# Kit_ELO_DEVMPDv1.net
KiCad netlist of a schematic drawn in Altium Designer
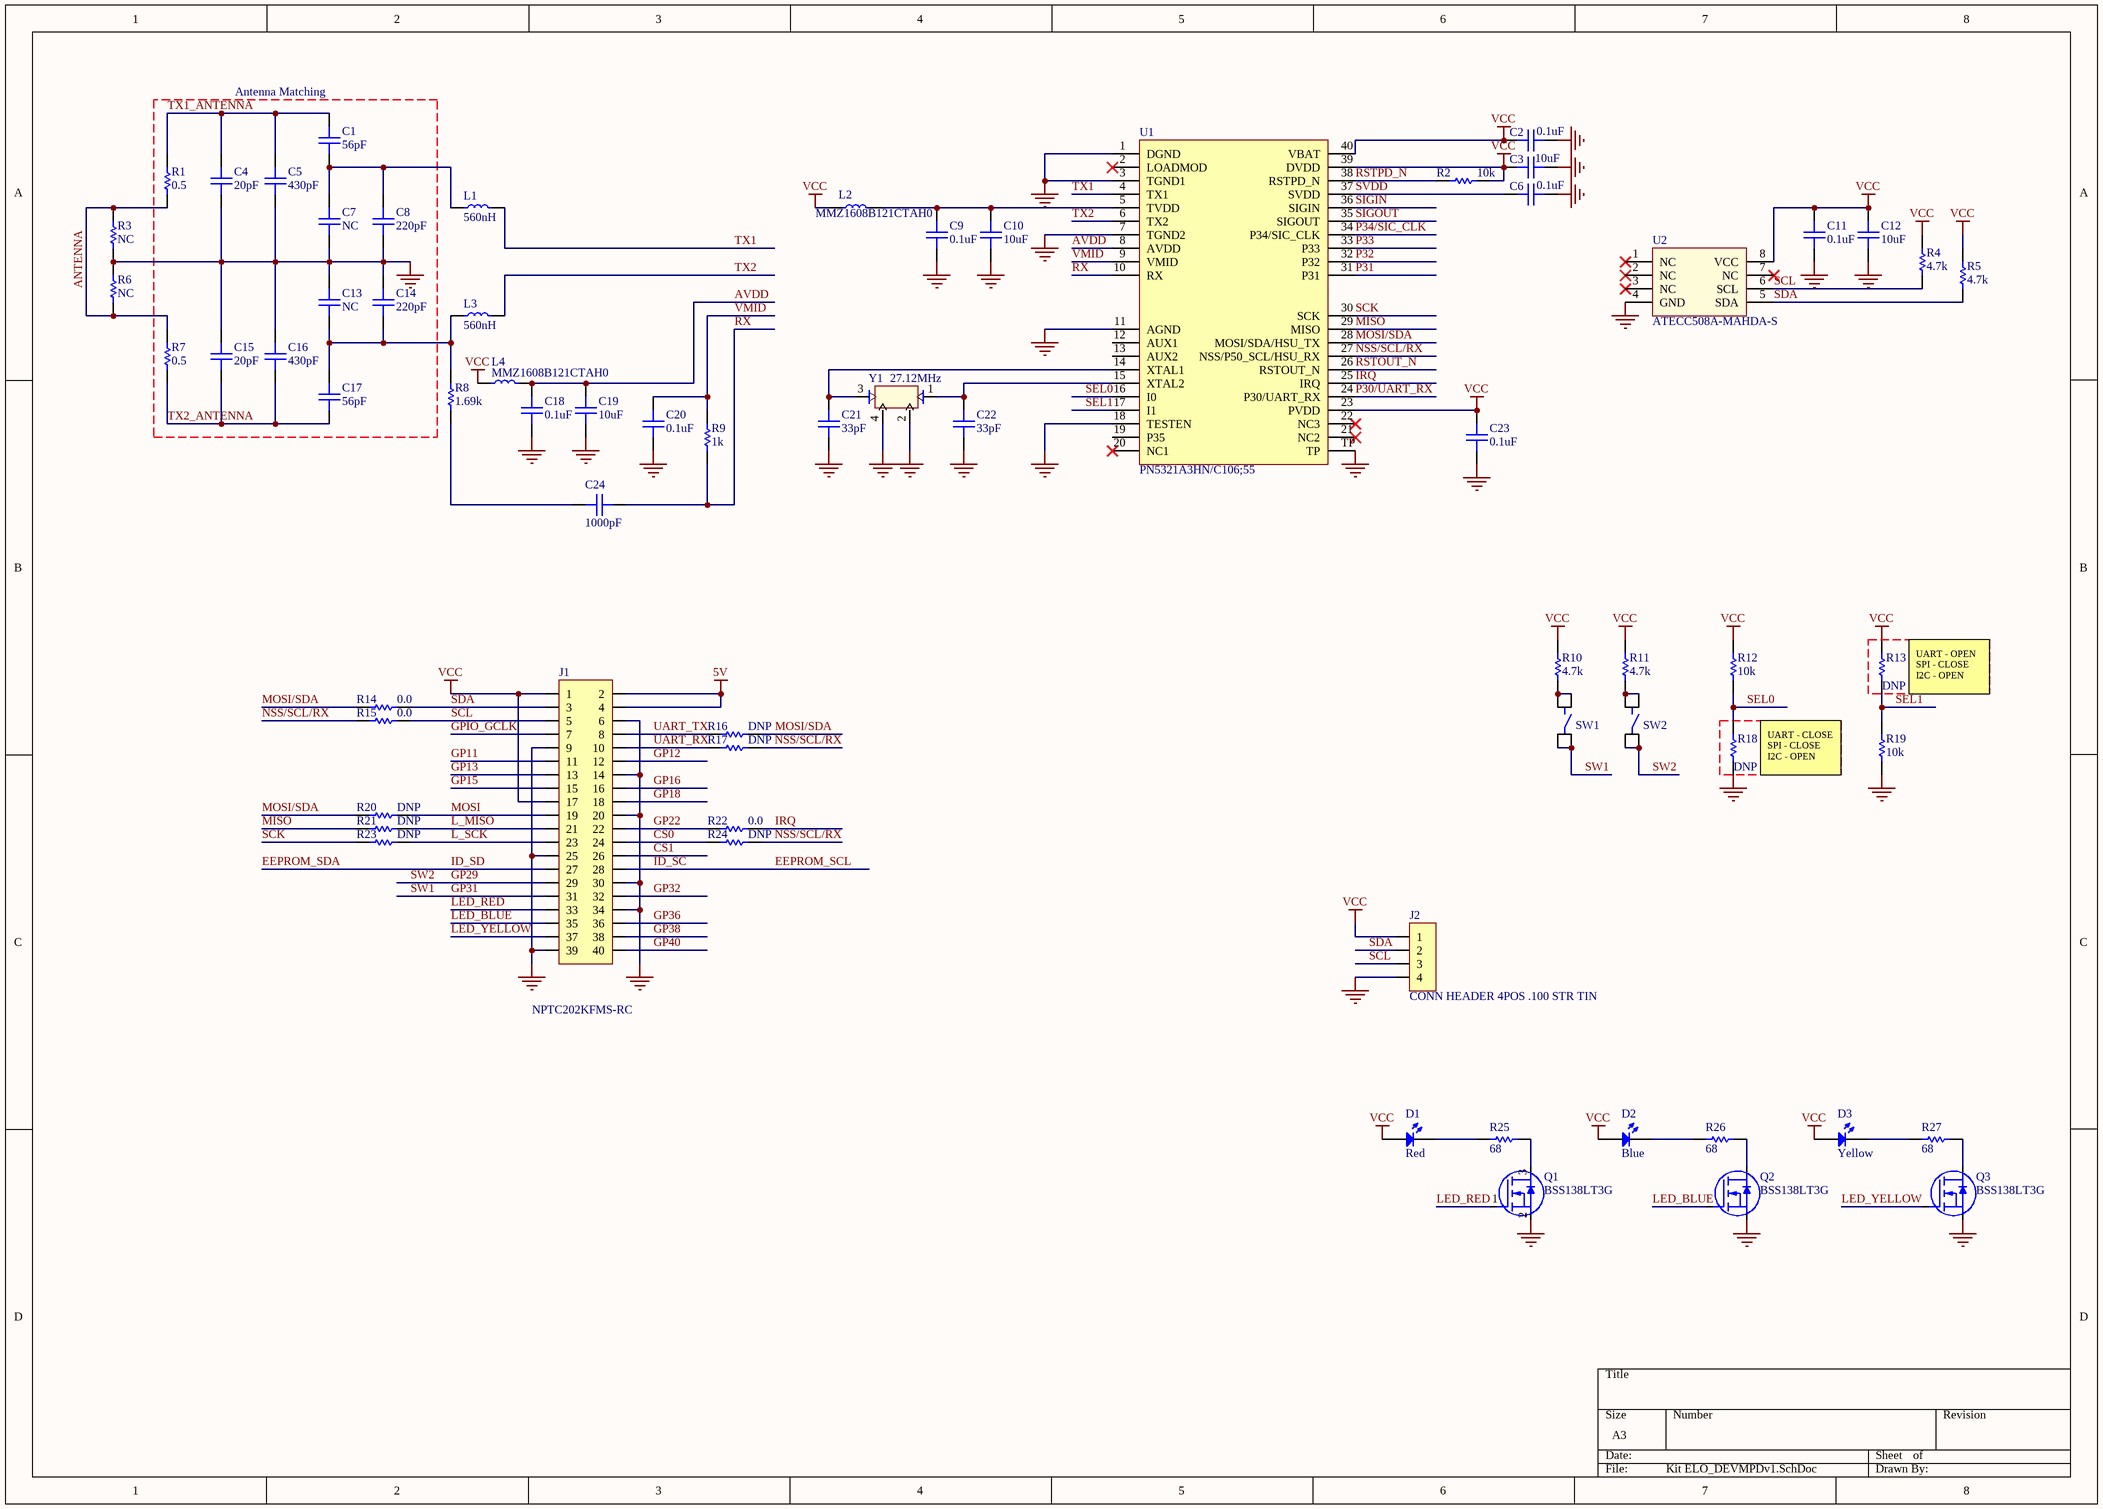
[diagram p0: Kit ELO_DEVMPDv1.SchDoc]

(export (version "E")
  (design (tool "Eeschema 10.0.6"))
  (components
    (comp (ref "C1")
      (value "56pF")
      (footprint "STD 0402 REFLOW CAP")
      (description "CAP CER 56PF 50V C0G/NP0 0402")
      (fields
        (field (name "MANUFACTURER") "Vishay Vitramon")
        (field (name "MANUFACTURER PART NUMBER") "VJ0402D560JXAAJ")
      )
      (libsource (lib "Discrete") (part "CAP CER 56PF 50V C0G/NP0 0402"))
    )
    (comp (ref "C2")
      (value "0.1uF")
      (footprint "STD 0402 REFLOW CAP")
      (description "CAP CER 0.1UF 10V X5R 0402")
      (fields
        (field (name "MANUFACTURER") "Murata Electronics North America")
        (field (name "MANUFACTURER PART NUMBER") "GRM155R61A104KA01D")
      )
      (libsource (lib "Schlib1") (part "CAP CER 0.1UF 10V X5R 0402"))
    )
    (comp (ref "C3")
      (value "10uF")
      (footprint "STD 0603 REFLOW CAP")
      (description "CAP CER 10UF 16V X5R 0603")
      (fields
        (field (name "MANUFACTURER") "Murata Electronics North America")
        (field (name "MANUFACTURER PART NUMBER") "GRM188R61C106KAALD")
      )
      (libsource (lib "Discrete") (part "CAP CER 10UF 16V X5R 0603"))
    )
    (comp (ref "C4")
      (value "20pF")
      (footprint "STD 0402 REFLOW CAP")
      (description "CAP CER 20PF 50V C0G/NP0 0402")
      (fields
        (field (name "MANUFACTURER") "KEMET")
        (field (name "MANUFACTURER PART NUMBER") "C0402C200J5GACTU")
      )
      (libsource (lib "Discrete") (part "CAP CER 20PF 50V C0G/NP0 0402"))
    )
    (comp (ref "C5")
      (value "430pF")
      (footprint "STD 0402 REFLOW CAP")
      (description "CAP CER 430PF 50V C0G/NP0 0402")
      (fields
        (field (name "MANUFACTURER") "Murata Electronics North America")
        (field (name "MANUFACTURER PART NUMBER") "GRM1555C1H431GA01D")
      )
      (libsource (lib "Discrete") (part "CAP CER 430PF 50V C0G/NP0 0402"))
    )
    (comp (ref "C6")
      (value "0.1uF")
      (footprint "STD 0402 REFLOW CAP")
      (description "CAP CER 0.1UF 10V X5R 0402")
      (fields
        (field (name "MANUFACTURER") "Murata Electronics North America")
        (field (name "MANUFACTURER PART NUMBER") "GRM155R61A104KA01D")
      )
      (libsource (lib "Schlib1") (part "CAP CER 0.1UF 10V X5R 0402"))
    )
    (comp (ref "C7")
      (value "NC")
      (footprint "STD 0402 REFLOW CAP")
      (fields
        (field (name "MANUFACTURER") "Murata Electronics North America")
        (field (name "MANUFACTURER PART NUMBER") "GRM155R61A104KA01D")
        (field (name "TOLERANCE") "±10%")
      )
      (libsource (lib "Schlib1") (part "CAP CER 0.1UF 10V X5R 0402"))
    )
    (comp (ref "C8")
      (value "220pF")
      (footprint "STD 0402 REFLOW CAP")
      (description "CAP CER 220PF 50V C0G/NP0 0402")
      (fields
        (field (name "MANUFACTURER") "Samsung Electro-Mechanics")
        (field (name "MANUFACTURER PART NUMBER") "CL05C221JB5NNNC")
      )
      (libsource (lib "Discrete") (part "CAP CER 220PF 50V C0G/NP0 0402"))
    )
    (comp (ref "C9")
      (value "0.1uF")
      (footprint "STD 0402 REFLOW CAP")
      (description "CAP CER 0.1UF 10V X5R 0402")
      (fields
        (field (name "MANUFACTURER") "Murata Electronics North America")
        (field (name "MANUFACTURER PART NUMBER") "GRM155R61A104KA01D")
      )
      (libsource (lib "Schlib1") (part "CAP CER 0.1UF 10V X5R 0402"))
    )
    (comp (ref "C10")
      (value "10uF")
      (footprint "STD 0603 REFLOW CAP")
      (description "CAP CER 10UF 16V X5R 0603")
      (fields
        (field (name "MANUFACTURER") "Murata Electronics North America")
        (field (name "MANUFACTURER PART NUMBER") "GRM188R61C106KAALD")
      )
      (libsource (lib "Discrete") (part "CAP CER 10UF 16V X5R 0603"))
    )
    (comp (ref "C11")
      (value "0.1uF")
      (footprint "STD 0402 REFLOW CAP")
      (description "CAP CER 0.1UF 10V X5R 0402")
      (fields
        (field (name "MANUFACTURER") "Murata Electronics North America")
        (field (name "MANUFACTURER PART NUMBER") "GRM155R61A104KA01D")
      )
      (libsource (lib "Schlib1") (part "CAP CER 0.1UF 10V X5R 0402"))
    )
    (comp (ref "C12")
      (value "10uF")
      (footprint "STD 0603 REFLOW CAP")
      (description "CAP CER 10UF 16V X5R 0603")
      (fields
        (field (name "MANUFACTURER") "Murata Electronics North America")
        (field (name "MANUFACTURER PART NUMBER") "GRM188R61C106KAALD")
      )
      (libsource (lib "Discrete") (part "CAP CER 10UF 16V X5R 0603"))
    )
    (comp (ref "C13")
      (value "NC")
      (footprint "STD 0402 REFLOW CAP")
      (fields
        (field (name "MANUFACTURER") "Murata Electronics North America")
        (field (name "MANUFACTURER PART NUMBER") "GRM155R61A104KA01D")
        (field (name "TOLERANCE") "±10%")
      )
      (libsource (lib "Schlib1") (part "CAP CER 0.1UF 10V X5R 0402"))
    )
    (comp (ref "C14")
      (value "220pF")
      (footprint "STD 0402 REFLOW CAP")
      (description "CAP CER 220PF 50V C0G/NP0 0402")
      (fields
        (field (name "MANUFACTURER") "Samsung Electro-Mechanics")
        (field (name "MANUFACTURER PART NUMBER") "CL05C221JB5NNNC")
      )
      (libsource (lib "Discrete") (part "CAP CER 220PF 50V C0G/NP0 0402"))
    )
    (comp (ref "C15")
      (value "20pF")
      (footprint "STD 0402 REFLOW CAP")
      (description "CAP CER 20PF 50V C0G/NP0 0402")
      (fields
        (field (name "MANUFACTURER") "KEMET")
        (field (name "MANUFACTURER PART NUMBER") "C0402C200J5GACTU")
      )
      (libsource (lib "Discrete") (part "CAP CER 20PF 50V C0G/NP0 0402"))
    )
    (comp (ref "C16")
      (value "430pF")
      (footprint "STD 0402 REFLOW CAP")
      (description "CAP CER 430PF 50V C0G/NP0 0402")
      (fields
        (field (name "MANUFACTURER") "Murata Electronics North America")
        (field (name "MANUFACTURER PART NUMBER") "GRM1555C1H431GA01D")
      )
      (libsource (lib "Discrete") (part "CAP CER 430PF 50V C0G/NP0 0402"))
    )
    (comp (ref "C17")
      (value "56pF")
      (footprint "STD 0402 REFLOW CAP")
      (description "CAP CER 56PF 50V C0G/NP0 0402")
      (fields
        (field (name "MANUFACTURER") "Vishay Vitramon")
        (field (name "MANUFACTURER PART NUMBER") "VJ0402D560JXAAJ")
      )
      (libsource (lib "Discrete") (part "CAP CER 56PF 50V C0G/NP0 0402"))
    )
    (comp (ref "C18")
      (value "0.1uF")
      (footprint "STD 0402 REFLOW CAP")
      (description "CAP CER 0.1UF 10V X5R 0402")
      (fields
        (field (name "MANUFACTURER") "Murata Electronics North America")
        (field (name "MANUFACTURER PART NUMBER") "GRM155R61A104KA01D")
      )
      (libsource (lib "Schlib1") (part "CAP CER 0.1UF 10V X5R 0402"))
    )
    (comp (ref "C19")
      (value "10uF")
      (footprint "STD 0603 REFLOW CAP")
      (description "CAP CER 10UF 16V X5R 0603")
      (fields
        (field (name "MANUFACTURER") "Murata Electronics North America")
        (field (name "MANUFACTURER PART NUMBER") "GRM188R61C106KAALD")
      )
      (libsource (lib "Discrete") (part "CAP CER 10UF 16V X5R 0603"))
    )
    (comp (ref "C20")
      (value "0.1uF")
      (footprint "STD 0402 REFLOW CAP")
      (description "CAP CER 0.1UF 10V X5R 0402")
      (fields
        (field (name "MANUFACTURER") "Murata Electronics North America")
        (field (name "MANUFACTURER PART NUMBER") "GRM155R61A104KA01D")
      )
      (libsource (lib "Schlib1") (part "CAP CER 0.1UF 10V X5R 0402"))
    )
    (comp (ref "C21")
      (value "33pF")
      (footprint "STD 0603 REFLOW CAP")
      (description "CAP CER 33PF 50V C0G/NP0 0603")
      (fields
        (field (name "MANUFACTURER") "Murata Electronics North America")
        (field (name "MANUFACTURER PART NUMBER") "GRM1885C1H330JA01D")
      )
      (libsource (lib "Schlib1") (part "CAP CER 33PF 50V C0G/NP0 0603"))
    )
    (comp (ref "C22")
      (value "33pF")
      (footprint "STD 0603 REFLOW CAP")
      (description "CAP CER 33PF 50V C0G/NP0 0603")
      (fields
        (field (name "MANUFACTURER") "Murata Electronics North America")
        (field (name "MANUFACTURER PART NUMBER") "GRM1885C1H330JA01D")
      )
      (libsource (lib "Schlib1") (part "CAP CER 33PF 50V C0G/NP0 0603"))
    )
    (comp (ref "C23")
      (value "0.1uF")
      (footprint "STD 0402 REFLOW CAP")
      (description "CAP CER 0.1UF 10V X5R 0402")
      (fields
        (field (name "MANUFACTURER") "Murata Electronics North America")
        (field (name "MANUFACTURER PART NUMBER") "GRM155R61A104KA01D")
      )
      (libsource (lib "Schlib1") (part "CAP CER 0.1UF 10V X5R 0402"))
    )
    (comp (ref "C24")
      (value "1000pF")
      (footprint "STD 0805 REFLOW CAP")
      (description "CAP CER 1000PF 50V C0G/NP0 0805")
      (fields
        (field (name "MANUFACTURER") "AVX Corporation")
        (field (name "MANUFACTURER PART NUMBER") "08055A102GAT2A")
      )
      (libsource (lib "Discrete") (part "CAP CER 1000PF 50V C0G/NP0 0805"))
    )
    (comp (ref "D1")
      (value "Red")
      (footprint "STD 0603 REFLOW LED RED")
      (description "LED RED CLEAR 0603 SMD")
      (fields
        (field (name "MANUFACTURER") "Lite-On Inc.")
        (field (name "MANUFACTURER PART NUMBER") "LTST-C190EKT")
      )
      (libsource (lib "Discrete") (part "LED RED CLEAR 0603 SMD"))
    )
    (comp (ref "D2")
      (value "Blue")
      (footprint "STD 0603 REFLOW LED BLUE")
      (description "LED BLUE CLEAR 0603 SMD")
      (fields
        (field (name "MANUFACTURER") "Lite-On Inc.")
        (field (name "MANUFACTURER PART NUMBER") "LTST-C193TBKT-5A")
      )
      (libsource (lib "Discrete") (part "LED BLUE CLEAR 0603 SMD"))
    )
    (comp (ref "D3")
      (value "Yellow")
      (footprint "STD 0603 REFLOW LED YELLOW")
      (description "LED YELLOW CLEAR 0603 SMD")
      (fields
        (field (name "MANUFACTURER") "Lite-On Inc.")
        (field (name "MANUFACTURER PART NUMBER") "LTST-C191KSKT")
      )
      (libsource (lib "Discrete") (part "LED YELLOW CLEAR 0603 SMD(LTST-C191KSKT)"))
    )
    (comp (ref "J1")
      (value "NPTC202KFMS-RC")
      (footprint "CONNECTOR 2.54 20X2 POS")
      (description "CONN FEMALE 40POS DL .1\" TIN SMD")
      (fields (field (name "MANUFACTURER") "Sullins Connector Solutions"))
      (libsource (lib "Mechanical") (part "CONN FEMALE 40POS DL .1{dblquote} TIN SMD"))
    )
    (comp (ref "J2")
      (value "CONN HEADER 4POS .100 STR TIN")
      (footprint ".100 MILS / 1MM / 4POS")
      (fields
        (field (name "MANUFACTURER") "Amphenol FCI")
        (field (name "MANUFACTURER PART NUMBER") "68002-404HLF")
      )
      (libsource (lib "Mechanical") (part "CONN HEADER 4POS .100 STR TIN"))
    )
    (comp (ref "L1")
      (value "560nH")
      (footprint "STD 0805 REFLOW IND")
      (description "FIXED IND 560NH 240MA 3.1 OHM")
      (fields
        (field (name "MANUFACTURER") "Pulse Electronics Network")
        (field (name "MANUFACTURER PART NUMBER") "PE-0805CM561JTT")
      )
      (libsource (lib "Schlib1") (part "FIXED IND 560NH 240MA 3.1 OHM"))
    )
    (comp (ref "L2")
      (value "MMZ1608B121CTAH0")
      (footprint "STD 0603 REFLOW IND")
      (description "FERRITE BEAD 120 OHM 0603 1LN")
      (fields (field (name "MANUFACTURER") "TDK Corporation"))
      (libsource (lib "Schlib1") (part "FERRITE BEAD 120 OHM 0603 1LN"))
    )
    (comp (ref "L3")
      (value "560nH")
      (footprint "STD 0805 REFLOW IND")
      (description "FIXED IND 560NH 240MA 3.1 OHM")
      (fields
        (field (name "MANUFACTURER") "Pulse Electronics Network")
        (field (name "MANUFACTURER PART NUMBER") "PE-0805CM561JTT")
      )
      (libsource (lib "Schlib1") (part "FIXED IND 560NH 240MA 3.1 OHM"))
    )
    (comp (ref "L4")
      (value "MMZ1608B121CTAH0")
      (footprint "STD 0603 REFLOW IND")
      (description "FERRITE BEAD 120 OHM 0603 1LN")
      (fields (field (name "MANUFACTURER") "TDK Corporation"))
      (libsource (lib "Schlib1") (part "FERRITE BEAD 120 OHM 0603 1LN"))
    )
    (comp (ref "Q1")
      (value "BSS138LT3G")
      (footprint "TO-236-3, SC-59, SOT-23-3")
      (description "MOSFET N-CH 50V 200MA SOT-23")
      (fields (field (name "MANUFACTURER") "ON Semiconductor"))
      (libsource (lib "") (part "MOSFET N-CH 50V 200MA SOT-23_1"))
    )
    (comp (ref "Q2")
      (value "BSS138LT3G")
      (footprint "TO-236-3, SC-59, SOT-23-3")
      (description "MOSFET N-CH 50V 200MA SOT-23")
      (fields (field (name "MANUFACTURER") "ON Semiconductor"))
      (libsource (lib "Discrete") (part "MOSFET N-CH 50V 200MA SOT-23"))
    )
    (comp (ref "Q3")
      (value "BSS138LT3G")
      (footprint "TO-236-3, SC-59, SOT-23-3")
      (description "MOSFET N-CH 50V 200MA SOT-23")
      (fields (field (name "MANUFACTURER") "ON Semiconductor"))
      (libsource (lib "Discrete") (part "MOSFET N-CH 50V 200MA SOT-23"))
    )
    (comp (ref "R1")
      (value "0.5")
      (footprint "STD 0402 REFLOW RES")
      (description "RES 0.5 OHM 1% 1/16W 0402")
      (fields
        (field (name "MANUFACTURER") "Yageo")
        (field (name "MANUFACTURER PART NUMBER") "RL0402FR-070R5L")
      )
      (libsource (lib "Discrete") (part "RES 0.5 OHM 1% 1/16W 0402"))
    )
    (comp (ref "R2")
      (value "10k")
      (footprint "STD 0402 REFLOW RES")
      (description "RES SMD 10K OHM 1% 1/16W 0402")
      (fields
        (field (name "MANUFACTURER") "Yageo")
        (field (name "MANUFACTURER PART NUMBER") "RC0402FR-0710KL")
      )
      (libsource (lib "Schlib1") (part "RES SMD 10K OHM 1% 1/16W 0402"))
    )
    (comp (ref "R3")
      (value "NC")
      (footprint "STD 0402 REFLOW RES")
      (fields
        (field (name "MANUFACTURER") "Yageo")
        (field (name "MANUFACTURER PART NUMBER") "RC0402FR-0710KL")
        (field (name "TOLERANCE") "±1%")
      )
      (libsource (lib "Schlib1") (part "RES SMD 10K OHM 1% 1/16W 0402"))
    )
    (comp (ref "R4")
      (value "4.7k")
      (footprint "STD 0402 REFLOW RES")
      (description "RES SMD 4.7K OHM 5% 1/10W 0402")
      (fields
        (field (name "MANUFACTURER") "Panasonic Electronic Components")
        (field (name "MANUFACTURER PART NUMBER") "ERJ-2GEJ472X")
      )
      (libsource (lib "Discrete") (part "RES SMD 4.7K OHM 5% 1/10W 0402"))
    )
    (comp (ref "R5")
      (value "4.7k")
      (footprint "STD 0402 REFLOW RES")
      (description "RES SMD 4.7K OHM 5% 1/10W 0402")
      (fields
        (field (name "MANUFACTURER") "Panasonic Electronic Components")
        (field (name "MANUFACTURER PART NUMBER") "ERJ-2GEJ472X")
      )
      (libsource (lib "Discrete") (part "RES SMD 4.7K OHM 5% 1/10W 0402"))
    )
    (comp (ref "R6")
      (value "NC")
      (footprint "STD 0402 REFLOW RES")
      (fields
        (field (name "MANUFACTURER") "Yageo")
        (field (name "MANUFACTURER PART NUMBER") "RC0402FR-0710KL")
        (field (name "TOLERANCE") "±1%")
      )
      (libsource (lib "Schlib1") (part "RES SMD 10K OHM 1% 1/16W 0402"))
    )
    (comp (ref "R7")
      (value "0.5")
      (footprint "STD 0402 REFLOW RES")
      (description "RES 0.5 OHM 1% 1/16W 0402")
      (fields
        (field (name "MANUFACTURER") "Yageo")
        (field (name "MANUFACTURER PART NUMBER") "RL0402FR-070R5L")
      )
      (libsource (lib "Discrete") (part "RES 0.5 OHM 1% 1/16W 0402"))
    )
    (comp (ref "R8")
      (value "1.69k")
      (footprint "STD 0402 REFLOW RES")
      (description "RES SMD 1.69K OHM 1% 1/16W 0402")
      (fields
        (field (name "MANUFACTURER") "Yageo")
        (field (name "MANUFACTURER PART NUMBER") "RC0402FR-071K69L")
      )
      (libsource (lib "Discrete") (part "RES SMD 1.69K OHM 1% 1/16W 0402"))
    )
    (comp (ref "R9")
      (value "1k")
      (footprint "STD 0402 REFLOW RES")
      (description "RES SMD 1K OHM 5% 1/16W 0402")
      (fields
        (field (name "MANUFACTURER") "Yageo")
        (field (name "MANUFACTURER PART NUMBER") "RC0402JR-071KL")
      )
      (libsource (lib "Discrete") (part "RES SMD 1K OHM 5% 1/16W 0402"))
    )
    (comp (ref "R10")
      (value "4.7k")
      (footprint "STD 0402 REFLOW RES")
      (description "RES SMD 4.7K OHM 5% 1/10W 0402")
      (fields
        (field (name "MANUFACTURER") "Panasonic Electronic Components")
        (field (name "MANUFACTURER PART NUMBER") "ERJ-2GEJ472X")
      )
      (libsource (lib "Discrete") (part "RES SMD 4.7K OHM 5% 1/10W 0402"))
    )
    (comp (ref "R11")
      (value "4.7k")
      (footprint "STD 0402 REFLOW RES")
      (description "RES SMD 4.7K OHM 5% 1/10W 0402")
      (fields
        (field (name "MANUFACTURER") "Panasonic Electronic Components")
        (field (name "MANUFACTURER PART NUMBER") "ERJ-2GEJ472X")
      )
      (libsource (lib "Discrete") (part "RES SMD 4.7K OHM 5% 1/10W 0402"))
    )
    (comp (ref "R12")
      (value "10k")
      (footprint "STD 0402 REFLOW RES")
      (description "RES SMD 10K OHM 1% 1/16W 0402")
      (fields
        (field (name "MANUFACTURER") "Yageo")
        (field (name "MANUFACTURER PART NUMBER") "RC0402FR-0710KL")
      )
      (libsource (lib "Schlib1") (part "RES SMD 10K OHM 1% 1/16W 0402"))
    )
    (comp (ref "R13")
      (value "DNP")
      (footprint "STD 0402 REFLOW RES")
      (description "RES SMD 0.0OHM JUMPER 1/16W 0402")
      (fields
        (field (name "MANUFACTURER") "Rohm Semiconductor")
        (field (name "MANUFACTURER PART NUMBER") "MCR01MZPJ000")
      )
      (libsource (lib "Discrete") (part "RES SMD 0.0OHM JUMPER 1/16W 0402"))
    )
    (comp (ref "R14")
      (value "0.0")
      (footprint "STD 0402 REFLOW RES")
      (description "RES SMD 0.0OHM JUMPER 1/16W 0402")
      (fields
        (field (name "MANUFACTURER") "Rohm Semiconductor")
        (field (name "MANUFACTURER PART NUMBER") "MCR01MZPJ000")
      )
      (libsource (lib "Discrete") (part "RES SMD 0.0OHM JUMPER 1/16W 0402"))
    )
    (comp (ref "R15")
      (value "0.0")
      (footprint "STD 0402 REFLOW RES")
      (description "RES SMD 0.0OHM JUMPER 1/16W 0402")
      (fields
        (field (name "MANUFACTURER") "Rohm Semiconductor")
        (field (name "MANUFACTURER PART NUMBER") "MCR01MZPJ000")
      )
      (libsource (lib "Discrete") (part "RES SMD 0.0OHM JUMPER 1/16W 0402"))
    )
    (comp (ref "R16")
      (value "DNP")
      (footprint "STD 0402 REFLOW RES")
      (description "RES SMD 0.0OHM JUMPER 1/16W 0402")
      (fields
        (field (name "MANUFACTURER") "Rohm Semiconductor")
        (field (name "MANUFACTURER PART NUMBER") "MCR01MZPJ000")
      )
      (libsource (lib "Discrete") (part "RES SMD 0.0OHM JUMPER 1/16W 0402"))
    )
    (comp (ref "R17")
      (value "DNP")
      (footprint "STD 0402 REFLOW RES")
      (description "RES SMD 0.0OHM JUMPER 1/16W 0402")
      (fields
        (field (name "MANUFACTURER") "Rohm Semiconductor")
        (field (name "MANUFACTURER PART NUMBER") "MCR01MZPJ000")
      )
      (libsource (lib "Discrete") (part "RES SMD 0.0OHM JUMPER 1/16W 0402"))
    )
    (comp (ref "R18")
      (value "DNP")
      (footprint "STD 0402 REFLOW RES")
      (description "RES SMD 0.0OHM JUMPER 1/16W 0402")
      (fields
        (field (name "MANUFACTURER") "Rohm Semiconductor")
        (field (name "MANUFACTURER PART NUMBER") "MCR01MZPJ000")
      )
      (libsource (lib "Discrete") (part "RES SMD 0.0OHM JUMPER 1/16W 0402"))
    )
    (comp (ref "R19")
      (value "10k")
      (footprint "STD 0402 REFLOW RES")
      (description "RES SMD 10K OHM 1% 1/16W 0402")
      (fields
        (field (name "MANUFACTURER") "Yageo")
        (field (name "MANUFACTURER PART NUMBER") "RC0402FR-0710KL")
      )
      (libsource (lib "Schlib1") (part "RES SMD 10K OHM 1% 1/16W 0402"))
    )
    (comp (ref "R20")
      (value "DNP")
      (footprint "STD 0402 REFLOW RES")
      (description "RES SMD 0.0OHM JUMPER 1/16W 0402")
      (fields
        (field (name "MANUFACTURER") "Rohm Semiconductor")
        (field (name "MANUFACTURER PART NUMBER") "MCR01MZPJ000")
      )
      (libsource (lib "Discrete") (part "RES SMD 0.0OHM JUMPER 1/16W 0402"))
    )
    (comp (ref "R21")
      (value "DNP")
      (footprint "STD 0402 REFLOW RES")
      (description "RES SMD 0.0OHM JUMPER 1/16W 0402")
      (fields
        (field (name "MANUFACTURER") "Rohm Semiconductor")
        (field (name "MANUFACTURER PART NUMBER") "MCR01MZPJ000")
      )
      (libsource (lib "Discrete") (part "RES SMD 0.0OHM JUMPER 1/16W 0402"))
    )
    (comp (ref "R22")
      (value "0.0")
      (footprint "STD 0402 REFLOW RES")
      (description "RES SMD 0.0OHM JUMPER 1/16W 0402")
      (fields
        (field (name "MANUFACTURER") "Rohm Semiconductor")
        (field (name "MANUFACTURER PART NUMBER") "MCR01MZPJ000")
      )
      (libsource (lib "Discrete") (part "RES SMD 0.0OHM JUMPER 1/16W 0402"))
    )
    (comp (ref "R23")
      (value "DNP")
      (footprint "STD 0402 REFLOW RES")
      (description "RES SMD 0.0OHM JUMPER 1/16W 0402")
      (fields
        (field (name "MANUFACTURER") "Rohm Semiconductor")
        (field (name "MANUFACTURER PART NUMBER") "MCR01MZPJ000")
      )
      (libsource (lib "Discrete") (part "RES SMD 0.0OHM JUMPER 1/16W 0402"))
    )
    (comp (ref "R24")
      (value "DNP")
      (footprint "STD 0402 REFLOW RES")
      (description "RES SMD 0.0OHM JUMPER 1/16W 0402")
      (fields
        (field (name "MANUFACTURER") "Rohm Semiconductor")
        (field (name "MANUFACTURER PART NUMBER") "MCR01MZPJ000")
      )
      (libsource (lib "Discrete") (part "RES SMD 0.0OHM JUMPER 1/16W 0402"))
    )
    (comp (ref "R25")
      (value "68")
      (footprint "STD 0402 REFLOW RES")
      (description "RES SMD 68 OHM 5% 1/10W 0402")
      (fields
        (field (name "MANUFACTURER") "Panasonic Electronic Components")
        (field (name "MANUFACTURER PART NUMBER") "ERJ-2GEJ680X")
      )
      (libsource (lib "Discrete") (part "RES SMD 68 OHM 5% 1/10W 0402"))
    )
    (comp (ref "R26")
      (value "68")
      (footprint "STD 0402 REFLOW RES")
      (description "RES SMD 68 OHM 5% 1/10W 0402")
      (fields
        (field (name "MANUFACTURER") "Panasonic Electronic Components")
        (field (name "MANUFACTURER PART NUMBER") "ERJ-2GEJ680X")
      )
      (libsource (lib "Discrete") (part "RES SMD 68 OHM 5% 1/10W 0402"))
    )
    (comp (ref "R27")
      (value "68")
      (footprint "STD 0402 REFLOW RES")
      (description "RES SMD 68 OHM 5% 1/10W 0402")
      (fields
        (field (name "MANUFACTURER") "Panasonic Electronic Components")
        (field (name "MANUFACTURER PART NUMBER") "ERJ-2GEJ680X")
      )
      (libsource (lib "Discrete") (part "RES SMD 68 OHM 5% 1/10W 0402"))
    )
    (comp (ref "SW1")
      (value "PTS645SL50SMTR92 LFS")
      (footprint "CK PTS645SM43SMTR92")
      (description "SWITCH TACTILE SPST-NO 0.05A 12V")
      (fields (field (name "MANUFACTURER") "C&K"))
      (libsource (lib "Mechanical") (part "SWITCH TACTILE SPST-NO 0.05A 12V (BLACK)"))
    )
    (comp (ref "SW2")
      (value "PTS645SL50SMTR92 LFS")
      (footprint "CK PTS645SM43SMTR92")
      (description "SWITCH TACTILE SPST-NO 0.05A 12V")
      (fields (field (name "MANUFACTURER") "C&K"))
      (libsource (lib "Mechanical") (part "SWITCH TACTILE SPST-NO 0.05A 12V (BLACK)"))
    )
    (comp (ref "U1")
      (value "PN5321A3HN/C106;55")
      (footprint "40-HVQFN (6x6)")
      (description "IC NFC NEAR FIELD CTLR 40HVQFN")
      (fields (field (name "MANUFACTURER") "NXP USA Inc."))
      (libsource (lib "Integrated") (part "PN5321A3HN/C106;55"))
    )
    (comp (ref "U2")
      (value "ATECC508A-MAHDA-S")
      (footprint "8-UDFN (2x3)")
      (description "AUTHENTICATION CHIP I2C 8-UDFN")
      (fields (field (name "MANUFACTURER") "Microchip Technology"))
      (libsource (lib "Integrated") (part "ATECC508A-MAHDA-S (2)"))
    )
    (comp (ref "Y1")
      (value "27.12MHz")
      (footprint "7M-27.120MEEQ-T")
      (description "CRYSTAL 27.1200MHZ 10PF SMD")
      (fields
        (field (name "MANUFACTURER") "TXC CORPORATION")
        (field (name "MANUFACTURER PART NUMBER") "7M-27.120MEEQ-T")
      )
      (libsource (lib "Discrete") (part "CRYSTAL 27.1200MHZ 10PF SMD"))
    )
  )
  (nets
    (net (code "1") (name "/ANTENNA") (class "Default")
      (node (ref "R1") (pin "1") (pinfunction "1_1") (pintype "passive"))
      (node (ref "R3") (pin "2") (pinfunction "2_2") (pintype "passive"))
      (node (ref "R6") (pin "1") (pinfunction "1_1") (pintype "passive"))
      (node (ref "R7") (pin "1") (pinfunction "1_1") (pintype "passive"))
    )
    (net (code "2") (name "/AVDD") (class "Default")
      (node (ref "C18") (pin "2") (pinfunction "2_2") (pintype "passive"))
      (node (ref "C19") (pin "2") (pinfunction "2_2") (pintype "passive"))
      (node (ref "L4") (pin "1") (pinfunction "1_1") (pintype "passive"))
      (node (ref "U1") (pin "8") (pinfunction "AVDD_8") (pintype "passive"))
    )
    (net (code "3") (name "/CS0") (class "Default")
      (node (ref "J1") (pin "24") (pinfunction "24_24") (pintype "passive"))
      (node (ref "R24") (pin "2") (pinfunction "2_2") (pintype "passive"))
    )
    (net (code "4") (name "/CS1") (class "Default")
      (node (ref "J1") (pin "26") (pinfunction "26_26") (pintype "passive"))
    )
    (net (code "5") (name "/EEPROM_SCL") (class "Default")
      (node (ref "J1") (pin "28") (pinfunction "28_28") (pintype "passive"))
    )
    (net (code "6") (name "/EEPROM_SDA") (class "Default")
      (node (ref "J1") (pin "27") (pinfunction "27_27") (pintype "passive"))
    )
    (net (code "7") (name "/GP11") (class "Default")
      (node (ref "J1") (pin "11") (pinfunction "11_11") (pintype "passive"))
    )
    (net (code "8") (name "/GP12") (class "Default")
      (node (ref "J1") (pin "12") (pinfunction "12_12") (pintype "passive"))
    )
    (net (code "9") (name "/GP13") (class "Default")
      (node (ref "J1") (pin "13") (pinfunction "13_13") (pintype "passive"))
    )
    (net (code "10") (name "/GP15") (class "Default")
      (node (ref "J1") (pin "15") (pinfunction "15_15") (pintype "passive"))
    )
    (net (code "11") (name "/GP16") (class "Default")
      (node (ref "J1") (pin "16") (pinfunction "16_16") (pintype "passive"))
    )
    (net (code "12") (name "/GP18") (class "Default")
      (node (ref "J1") (pin "18") (pinfunction "18_18") (pintype "passive"))
    )
    (net (code "13") (name "/GP22") (class "Default")
      (node (ref "J1") (pin "22") (pinfunction "22_22") (pintype "passive"))
      (node (ref "R22") (pin "2") (pinfunction "2_2") (pintype "passive"))
    )
    (net (code "14") (name "/GP29") (class "Default")
      (node (ref "J1") (pin "29") (pinfunction "29_29") (pintype "passive"))
      (node (ref "SW2") (pin "3") (pinfunction "3_3") (pintype "passive"))
      (node (ref "SW2") (pin "4") (pinfunction "4_4") (pintype "passive"))
    )
    (net (code "15") (name "/GP31") (class "Default")
      (node (ref "J1") (pin "31") (pinfunction "31_31") (pintype "passive"))
      (node (ref "SW1") (pin "3") (pinfunction "3_3") (pintype "passive"))
      (node (ref "SW1") (pin "4") (pinfunction "4_4") (pintype "passive"))
    )
    (net (code "16") (name "/GP32") (class "Default")
      (node (ref "J1") (pin "32") (pinfunction "32_32") (pintype "passive"))
    )
    (net (code "17") (name "/GP36") (class "Default")
      (node (ref "J1") (pin "36") (pinfunction "36_36") (pintype "passive"))
    )
    (net (code "18") (name "/GP38") (class "Default")
      (node (ref "J1") (pin "38") (pinfunction "38_38") (pintype "passive"))
    )
    (net (code "19") (name "/GP40") (class "Default")
      (node (ref "J1") (pin "40") (pinfunction "40_40") (pintype "passive"))
    )
    (net (code "20") (name "/GPIO_GCLK") (class "Default")
      (node (ref "J1") (pin "7") (pinfunction "7_7") (pintype "passive"))
    )
    (net (code "21") (name "/IRQ") (class "Default")
      (node (ref "R22") (pin "1") (pinfunction "1_1") (pintype "passive"))
      (node (ref "U1") (pin "25") (pinfunction "IRQ_25") (pintype "passive"))
    )
    (net (code "22") (name "/LED_BLUE") (class "Default")
      (node (ref "J1") (pin "35") (pinfunction "35_35") (pintype "passive"))
      (node (ref "Q2") (pin "1") (pinfunction "G_1") (pintype "passive"))
    )
    (net (code "23") (name "/LED_RED") (class "Default")
      (node (ref "J1") (pin "33") (pinfunction "33_33") (pintype "passive"))
      (node (ref "Q1") (pin "1") (pinfunction "G_1") (pintype "passive"))
    )
    (net (code "24") (name "/LED_YELLOW") (class "Default")
      (node (ref "J1") (pin "37") (pinfunction "37_37") (pintype "passive"))
      (node (ref "Q3") (pin "1") (pinfunction "G_1") (pintype "passive"))
    )
    (net (code "25") (name "/L_MISO") (class "Default")
      (node (ref "J1") (pin "21") (pinfunction "21_21") (pintype "passive"))
      (node (ref "R21") (pin "2") (pinfunction "2_2") (pintype "passive"))
    )
    (net (code "26") (name "/L_SCK") (class "Default")
      (node (ref "J1") (pin "23") (pinfunction "23_23") (pintype "passive"))
      (node (ref "R23") (pin "2") (pinfunction "2_2") (pintype "passive"))
    )
    (net (code "27") (name "/MISO") (class "Default")
      (node (ref "R21") (pin "1") (pinfunction "1_1") (pintype "passive"))
      (node (ref "U1") (pin "29") (pinfunction "MISO_29") (pintype "passive"))
    )
    (net (code "28") (name "/MOSI") (class "Default")
      (node (ref "J1") (pin "19") (pinfunction "19_19") (pintype "passive"))
      (node (ref "R20") (pin "2") (pinfunction "2_2") (pintype "passive"))
    )
    (net (code "29") (name "/MOSI{slash}SDA") (class "Default")
      (node (ref "R14") (pin "1") (pinfunction "1_1") (pintype "passive"))
      (node (ref "R16") (pin "1") (pinfunction "1_1") (pintype "passive"))
      (node (ref "R20") (pin "1") (pinfunction "1_1") (pintype "passive"))
      (node (ref "U1") (pin "28") (pinfunction "MOSI/SDA/HSU_TX_28") (pintype "passive"))
    )
    (net (code "30") (name "/NSS{slash}SCL{slash}RX") (class "Default")
      (node (ref "R15") (pin "1") (pinfunction "1_1") (pintype "passive"))
      (node (ref "R17") (pin "1") (pinfunction "1_1") (pintype "passive"))
      (node (ref "R24") (pin "1") (pinfunction "1_1") (pintype "passive"))
      (node (ref "U1") (pin "27") (pinfunction "NSS/P50_SCL/HSU_RX_27") (pintype "passive"))
    )
    (net (code "31") (name "/P30{slash}UART_RX") (class "Default")
      (node (ref "U1") (pin "24") (pinfunction "P30/UART_RX_24") (pintype "passive"))
    )
    (net (code "32") (name "/P31") (class "Default")
      (node (ref "U1") (pin "31") (pinfunction "P31_31") (pintype "passive"))
    )
    (net (code "33") (name "/P32") (class "Default")
      (node (ref "U1") (pin "32") (pinfunction "P32_32") (pintype "passive"))
    )
    (net (code "34") (name "/P33") (class "Default")
      (node (ref "U1") (pin "33") (pinfunction "P33_33") (pintype "passive"))
    )
    (net (code "35") (name "/P34{slash}SIC_CLK") (class "Default")
      (node (ref "U1") (pin "34") (pinfunction "P34/SIC_CLK_34") (pintype "passive"))
    )
    (net (code "36") (name "/RSTOUT_N") (class "Default")
      (node (ref "U1") (pin "26") (pinfunction "RSTOUT_N_26") (pintype "passive"))
    )
    (net (code "37") (name "/RSTPD_N") (class "Default")
      (node (ref "R2") (pin "2") (pinfunction "2_2") (pintype "passive"))
      (node (ref "U1") (pin "38") (pinfunction "RSTPD_N_38") (pintype "passive"))
    )
    (net (code "38") (name "/RX") (class "Default")
      (node (ref "C24") (pin "1") (pinfunction "1_1") (pintype "passive"))
      (node (ref "R9") (pin "1") (pinfunction "1_1") (pintype "passive"))
      (node (ref "U1") (pin "10") (pinfunction "RX_10") (pintype "passive"))
    )
    (net (code "39") (name "/SCK") (class "Default")
      (node (ref "R23") (pin "1") (pinfunction "1_1") (pintype "passive"))
      (node (ref "U1") (pin "30") (pinfunction "SCK_30") (pintype "passive"))
    )
    (net (code "40") (name "/SCL") (class "Default")
      (node (ref "J1") (pin "5") (pinfunction "5_5") (pintype "passive"))
      (node (ref "J2") (pin "3") (pinfunction "3_3") (pintype "passive"))
      (node (ref "R15") (pin "2") (pinfunction "2_2") (pintype "passive"))
      (node (ref "R4") (pin "1") (pinfunction "1_1") (pintype "passive"))
      (node (ref "U2") (pin "6") (pinfunction "SCL_6") (pintype "passive"))
    )
    (net (code "41") (name "/SDA") (class "Default")
      (node (ref "J1") (pin "3") (pinfunction "3_3") (pintype "passive"))
      (node (ref "J2") (pin "2") (pinfunction "2_2") (pintype "passive"))
      (node (ref "R14") (pin "2") (pinfunction "2_2") (pintype "passive"))
      (node (ref "R5") (pin "1") (pinfunction "1_1") (pintype "passive"))
      (node (ref "U2") (pin "5") (pinfunction "SDA_5") (pintype "passive"))
    )
    (net (code "42") (name "/SEL0") (class "Default")
      (node (ref "R12") (pin "1") (pinfunction "1_1") (pintype "passive"))
      (node (ref "R18") (pin "2") (pinfunction "2_2") (pintype "passive"))
      (node (ref "U1") (pin "16") (pinfunction "I0_16") (pintype "passive"))
    )
    (net (code "43") (name "/SEL1") (class "Default")
      (node (ref "R13") (pin "1") (pinfunction "1_1") (pintype "passive"))
      (node (ref "R19") (pin "2") (pinfunction "2_2") (pintype "passive"))
      (node (ref "U1") (pin "17") (pinfunction "I1_17") (pintype "passive"))
    )
    (net (code "44") (name "/SIGIN") (class "Default")
      (node (ref "U1") (pin "36") (pinfunction "SIGIN_36") (pintype "passive"))
    )
    (net (code "45") (name "/SIGOUT") (class "Default")
      (node (ref "U1") (pin "35") (pinfunction "SIGOUT_35") (pintype "passive"))
    )
    (net (code "46") (name "/SVDD") (class "Default")
      (node (ref "C6") (pin "2") (pinfunction "2_2") (pintype "passive"))
      (node (ref "U1") (pin "37") (pinfunction "SVDD_37") (pintype "passive"))
    )
    (net (code "47") (name "/TX1") (class "Default")
      (node (ref "L1") (pin "1") (pinfunction "1_1") (pintype "passive"))
      (node (ref "U1") (pin "4") (pinfunction "TX1_4") (pintype "passive"))
    )
    (net (code "48") (name "/TX1_ANTENNA") (class "Default")
      (node (ref "C1") (pin "2") (pinfunction "2_2") (pintype "passive"))
      (node (ref "C4") (pin "2") (pinfunction "2_2") (pintype "passive"))
      (node (ref "C5") (pin "2") (pinfunction "2_2") (pintype "passive"))
      (node (ref "R1") (pin "2") (pinfunction "2_2") (pintype "passive"))
    )
    (net (code "49") (name "/TX2") (class "Default")
      (node (ref "L3") (pin "1") (pinfunction "1_1") (pintype "passive"))
      (node (ref "U1") (pin "6") (pinfunction "TX2_6") (pintype "passive"))
    )
    (net (code "50") (name "/TX2_ANTENNA") (class "Default")
      (node (ref "C15") (pin "1") (pinfunction "1_1") (pintype "passive"))
      (node (ref "C16") (pin "1") (pinfunction "1_1") (pintype "passive"))
      (node (ref "C17") (pin "1") (pinfunction "1_1") (pintype "passive"))
      (node (ref "R7") (pin "2") (pinfunction "2_2") (pintype "passive"))
    )
    (net (code "51") (name "/UART_RX") (class "Default")
      (node (ref "J1") (pin "10") (pinfunction "10_10") (pintype "passive"))
      (node (ref "R17") (pin "2") (pinfunction "2_2") (pintype "passive"))
    )
    (net (code "52") (name "/UART_TX") (class "Default")
      (node (ref "J1") (pin "8") (pinfunction "8_8") (pintype "passive"))
      (node (ref "R16") (pin "2") (pinfunction "2_2") (pintype "passive"))
    )
    (net (code "53") (name "/VMID") (class "Default")
      (node (ref "C20") (pin "2") (pinfunction "2_2") (pintype "passive"))
      (node (ref "R9") (pin "2") (pinfunction "2_2") (pintype "passive"))
      (node (ref "U1") (pin "9") (pinfunction "VMID_9") (pintype "passive"))
    )
    (net (code "54") (name "5V") (class "Default")
      (node (ref "J1") (pin "2") (pinfunction "2_2") (pintype "passive"))
      (node (ref "J1") (pin "4") (pinfunction "4_4") (pintype "passive"))
    )
    (net (code "55") (name "GND") (class "Default")
      (node (ref "C10") (pin "1") (pinfunction "1_1") (pintype "passive"))
      (node (ref "C11") (pin "1") (pinfunction "1_1") (pintype "passive"))
      (node (ref "C12") (pin "2") (pinfunction "2_2") (pintype "passive"))
      (node (ref "C13") (pin "1") (pinfunction "1_1") (pintype "passive"))
      (node (ref "C14") (pin "2") (pinfunction "2_2") (pintype "passive"))
      (node (ref "C15") (pin "2") (pinfunction "2_2") (pintype "passive"))
      (node (ref "C16") (pin "2") (pinfunction "2_2") (pintype "passive"))
      (node (ref "C18") (pin "1") (pinfunction "1_1") (pintype "passive"))
      (node (ref "C19") (pin "1") (pinfunction "1_1") (pintype "passive"))
      (node (ref "C2") (pin "1") (pinfunction "1_1") (pintype "passive"))
      (node (ref "C20") (pin "1") (pinfunction "1_1") (pintype "passive"))
      (node (ref "C21") (pin "1") (pinfunction "1_1") (pintype "passive"))
      (node (ref "C22") (pin "1") (pinfunction "1_1") (pintype "passive"))
      (node (ref "C23") (pin "1") (pinfunction "1_1") (pintype "passive"))
      (node (ref "C3") (pin "2") (pinfunction "2_2") (pintype "passive"))
      (node (ref "C4") (pin "1") (pinfunction "1_1") (pintype "passive"))
      (node (ref "C5") (pin "1") (pinfunction "1_1") (pintype "passive"))
      (node (ref "C6") (pin "1") (pinfunction "1_1") (pintype "passive"))
      (node (ref "C7") (pin "2") (pinfunction "2_2") (pintype "passive"))
      (node (ref "C8") (pin "1") (pinfunction "1_1") (pintype "passive"))
      (node (ref "C9") (pin "1") (pinfunction "1_1") (pintype "passive"))
      (node (ref "J1") (pin "14") (pinfunction "14_14") (pintype "passive"))
      (node (ref "J1") (pin "20") (pinfunction "20_20") (pintype "passive"))
      (node (ref "J1") (pin "25") (pinfunction "25_25") (pintype "passive"))
      (node (ref "J1") (pin "30") (pinfunction "30_30") (pintype "passive"))
      (node (ref "J1") (pin "34") (pinfunction "34_34") (pintype "passive"))
      (node (ref "J1") (pin "39") (pinfunction "39_39") (pintype "passive"))
      (node (ref "J1") (pin "6") (pinfunction "6_6") (pintype "passive"))
      (node (ref "J1") (pin "9") (pinfunction "9_9") (pintype "passive"))
      (node (ref "J2") (pin "4") (pinfunction "4_4") (pintype "passive"))
      (node (ref "Q1") (pin "2") (pinfunction "S_2") (pintype "passive"))
      (node (ref "Q2") (pin "2") (pinfunction "S_2") (pintype "passive"))
      (node (ref "Q3") (pin "2") (pinfunction "S_2") (pintype "passive"))
      (node (ref "R18") (pin "1") (pinfunction "1_1") (pintype "passive"))
      (node (ref "R19") (pin "1") (pinfunction "1_1") (pintype "passive"))
      (node (ref "R3") (pin "1") (pinfunction "1_1") (pintype "passive"))
      (node (ref "R6") (pin "2") (pinfunction "2_2") (pintype "passive"))
      (node (ref "U1") (pin "1") (pinfunction "DGND_1") (pintype "passive"))
      (node (ref "U1") (pin "11") (pinfunction "AGND_11") (pintype "passive"))
      (node (ref "U1") (pin "18") (pinfunction "TESTEN_18") (pintype "passive"))
      (node (ref "U1") (pin "3") (pinfunction "TGND1_3") (pintype "passive"))
      (node (ref "U1") (pin "7") (pinfunction "TGND2_7") (pintype "passive"))
      (node (ref "U1") (pin "TP") (pinfunction "TP_TP") (pintype "passive"))
      (node (ref "U2") (pin "4") (pinfunction "GND_4") (pintype "power_in"))
      (node (ref "Y1") (pin "2") (pinfunction "2_2") (pintype "passive"))
      (node (ref "Y1") (pin "4") (pinfunction "4_4") (pintype "passive"))
    )
    (net (code "56") (name "Net-(C1-Pad1)") (class "Default")
      (node (ref "C1") (pin "1") (pinfunction "1_1") (pintype "passive"))
      (node (ref "C7") (pin "1") (pinfunction "1_1") (pintype "passive"))
      (node (ref "C8") (pin "2") (pinfunction "2_2") (pintype "passive"))
      (node (ref "L1") (pin "2") (pinfunction "2_2") (pintype "passive"))
    )
    (net (code "57") (name "Net-(C13-Pad2)") (class "Default")
      (node (ref "C13") (pin "2") (pinfunction "2_2") (pintype "passive"))
      (node (ref "C14") (pin "1") (pinfunction "1_1") (pintype "passive"))
      (node (ref "C17") (pin "2") (pinfunction "2_2") (pintype "passive"))
      (node (ref "L3") (pin "2") (pinfunction "2_2") (pintype "passive"))
      (node (ref "R8") (pin "2") (pinfunction "2_2") (pintype "passive"))
    )
    (net (code "58") (name "Net-(C24-Pad2)") (class "Default")
      (node (ref "C24") (pin "2") (pinfunction "2_2") (pintype "passive"))
      (node (ref "R8") (pin "1") (pinfunction "1_1") (pintype "passive"))
    )
    (net (code "59") (name "Net-(D1-K)") (class "Default")
      (node (ref "D1") (pin "2") (pinfunction "K_2") (pintype "passive"))
      (node (ref "R25") (pin "1") (pinfunction "1_1") (pintype "passive"))
    )
    (net (code "60") (name "Net-(D2-K)") (class "Default")
      (node (ref "D2") (pin "2") (pinfunction "K_2") (pintype "passive"))
      (node (ref "R26") (pin "1") (pinfunction "1_1") (pintype "passive"))
    )
    (net (code "61") (name "Net-(D3-K)") (class "Default")
      (node (ref "D3") (pin "2") (pinfunction "K_2") (pintype "passive"))
      (node (ref "R27") (pin "1") (pinfunction "1_1") (pintype "passive"))
    )
    (net (code "62") (name "Net-(Q1-D)") (class "Default")
      (node (ref "Q1") (pin "3") (pinfunction "D_3") (pintype "passive"))
      (node (ref "R25") (pin "2") (pinfunction "2_2") (pintype "passive"))
    )
    (net (code "63") (name "Net-(Q2-D)") (class "Default")
      (node (ref "Q2") (pin "3") (pinfunction "D_3") (pintype "passive"))
      (node (ref "R26") (pin "2") (pinfunction "2_2") (pintype "passive"))
    )
    (net (code "64") (name "Net-(Q3-D)") (class "Default")
      (node (ref "Q3") (pin "3") (pinfunction "D_3") (pintype "passive"))
      (node (ref "R27") (pin "2") (pinfunction "2_2") (pintype "passive"))
    )
    (net (code "65") (name "Net-(R10-Pad1)") (class "Default")
      (node (ref "R10") (pin "1") (pinfunction "1_1") (pintype "passive"))
      (node (ref "SW1") (pin "1") (pinfunction "1_1") (pintype "passive"))
      (node (ref "SW1") (pin "2") (pinfunction "2_2") (pintype "passive"))
    )
    (net (code "66") (name "Net-(R11-Pad1)") (class "Default")
      (node (ref "R11") (pin "1") (pinfunction "1_1") (pintype "passive"))
      (node (ref "SW2") (pin "1") (pinfunction "1_1") (pintype "passive"))
      (node (ref "SW2") (pin "2") (pinfunction "2_2") (pintype "passive"))
    )
    (net (code "67") (name "Net-(U1-TVDD)") (class "Default")
      (node (ref "C10") (pin "2") (pinfunction "2_2") (pintype "passive"))
      (node (ref "C9") (pin "2") (pinfunction "2_2") (pintype "passive"))
      (node (ref "L2") (pin "1") (pinfunction "1_1") (pintype "passive"))
      (node (ref "U1") (pin "5") (pinfunction "TVDD_5") (pintype "passive"))
    )
    (net (code "68") (name "Net-(U1-XTAL1)") (class "Default")
      (node (ref "C21") (pin "2") (pinfunction "2_2") (pintype "passive"))
      (node (ref "U1") (pin "14") (pinfunction "XTAL1_14") (pintype "passive"))
      (node (ref "Y1") (pin "3") (pinfunction "3_3") (pintype "passive"))
    )
    (net (code "69") (name "Net-(U1-XTAL2)") (class "Default")
      (node (ref "C22") (pin "2") (pinfunction "2_2") (pintype "passive"))
      (node (ref "U1") (pin "15") (pinfunction "XTAL2_15") (pintype "passive"))
      (node (ref "Y1") (pin "1") (pinfunction "1_1") (pintype "passive"))
    )
    (net (code "70") (name "VCC") (class "Default")
      (node (ref "C11") (pin "2") (pinfunction "2_2") (pintype "passive"))
      (node (ref "C12") (pin "1") (pinfunction "1_1") (pintype "passive"))
      (node (ref "C2") (pin "2") (pinfunction "2_2") (pintype "passive"))
      (node (ref "C23") (pin "2") (pinfunction "2_2") (pintype "passive"))
      (node (ref "C3") (pin "1") (pinfunction "1_1") (pintype "passive"))
      (node (ref "D1") (pin "1") (pinfunction "A_1") (pintype "passive"))
      (node (ref "D2") (pin "1") (pinfunction "A_1") (pintype "passive"))
      (node (ref "D3") (pin "1") (pinfunction "A_1") (pintype "passive"))
      (node (ref "J1") (pin "1") (pinfunction "1_1") (pintype "passive"))
      (node (ref "J1") (pin "17") (pinfunction "17_17") (pintype "passive"))
      (node (ref "J2") (pin "1") (pinfunction "1_1") (pintype "passive"))
      (node (ref "L2") (pin "2") (pinfunction "2_2") (pintype "passive"))
      (node (ref "L4") (pin "2") (pinfunction "2_2") (pintype "passive"))
      (node (ref "R10") (pin "2") (pinfunction "2_2") (pintype "passive"))
      (node (ref "R11") (pin "2") (pinfunction "2_2") (pintype "passive"))
      (node (ref "R12") (pin "2") (pinfunction "2_2") (pintype "passive"))
      (node (ref "R13") (pin "2") (pinfunction "2_2") (pintype "passive"))
      (node (ref "R2") (pin "1") (pinfunction "1_1") (pintype "passive"))
      (node (ref "R4") (pin "2") (pinfunction "2_2") (pintype "passive"))
      (node (ref "R5") (pin "2") (pinfunction "2_2") (pintype "passive"))
      (node (ref "U1") (pin "23") (pinfunction "PVDD_23") (pintype "passive"))
      (node (ref "U1") (pin "39") (pinfunction "DVDD_39") (pintype "passive"))
      (node (ref "U1") (pin "40") (pinfunction "VBAT_40") (pintype "passive"))
      (node (ref "U2") (pin "8") (pinfunction "VCC_8") (pintype "power_in"))
    )
    (net (code "71") (name "unconnected-(U1-AUX1-Pad12)") (class "Default")
      (node (ref "U1") (pin "12") (pinfunction "AUX1_12") (pintype "passive"))
    )
    (net (code "72") (name "unconnected-(U1-AUX2-Pad13)") (class "Default")
      (node (ref "U1") (pin "13") (pinfunction "AUX2_13") (pintype "passive"))
    )
    (net (code "73") (name "unconnected-(U1-LOADMOD-Pad2)") (class "Default")
      (node (ref "U1") (pin "2") (pinfunction "LOADMOD_2") (pintype "passive+no_connect"))
    )
    (net (code "74") (name "unconnected-(U1-NC1-Pad20)") (class "Default")
      (node (ref "U1") (pin "20") (pinfunction "NC1_20") (pintype "passive+no_connect"))
    )
    (net (code "75") (name "unconnected-(U1-NC2-Pad21)") (class "Default")
      (node (ref "U1") (pin "21") (pinfunction "NC2_21") (pintype "passive+no_connect"))
    )
    (net (code "76") (name "unconnected-(U1-NC3-Pad22)") (class "Default")
      (node (ref "U1") (pin "22") (pinfunction "NC3_22") (pintype "passive+no_connect"))
    )
    (net (code "77") (name "unconnected-(U1-P35-Pad19)") (class "Default")
      (node (ref "U1") (pin "19") (pinfunction "P35_19") (pintype "passive"))
    )
    (net (code "78") (name "unconnected-(U2-NC-Pad1)") (class "Default")
      (node (ref "U2") (pin "1") (pinfunction "NC_1") (pintype "passive+no_connect"))
    )
    (net (code "79") (name "unconnected-(U2-NC-Pad2)") (class "Default")
      (node (ref "U2") (pin "2") (pinfunction "NC_2") (pintype "passive+no_connect"))
    )
    (net (code "80") (name "unconnected-(U2-NC-Pad3)") (class "Default")
      (node (ref "U2") (pin "3") (pinfunction "NC_3") (pintype "passive+no_connect"))
    )
    (net (code "81") (name "unconnected-(U2-NC-Pad7)") (class "Default")
      (node (ref "U2") (pin "7") (pinfunction "NC_7") (pintype "power_in+no_connect"))
    )
  )
)
